# expansion-original-.net
KiCad netlist of a schematic drawn in EAGLE
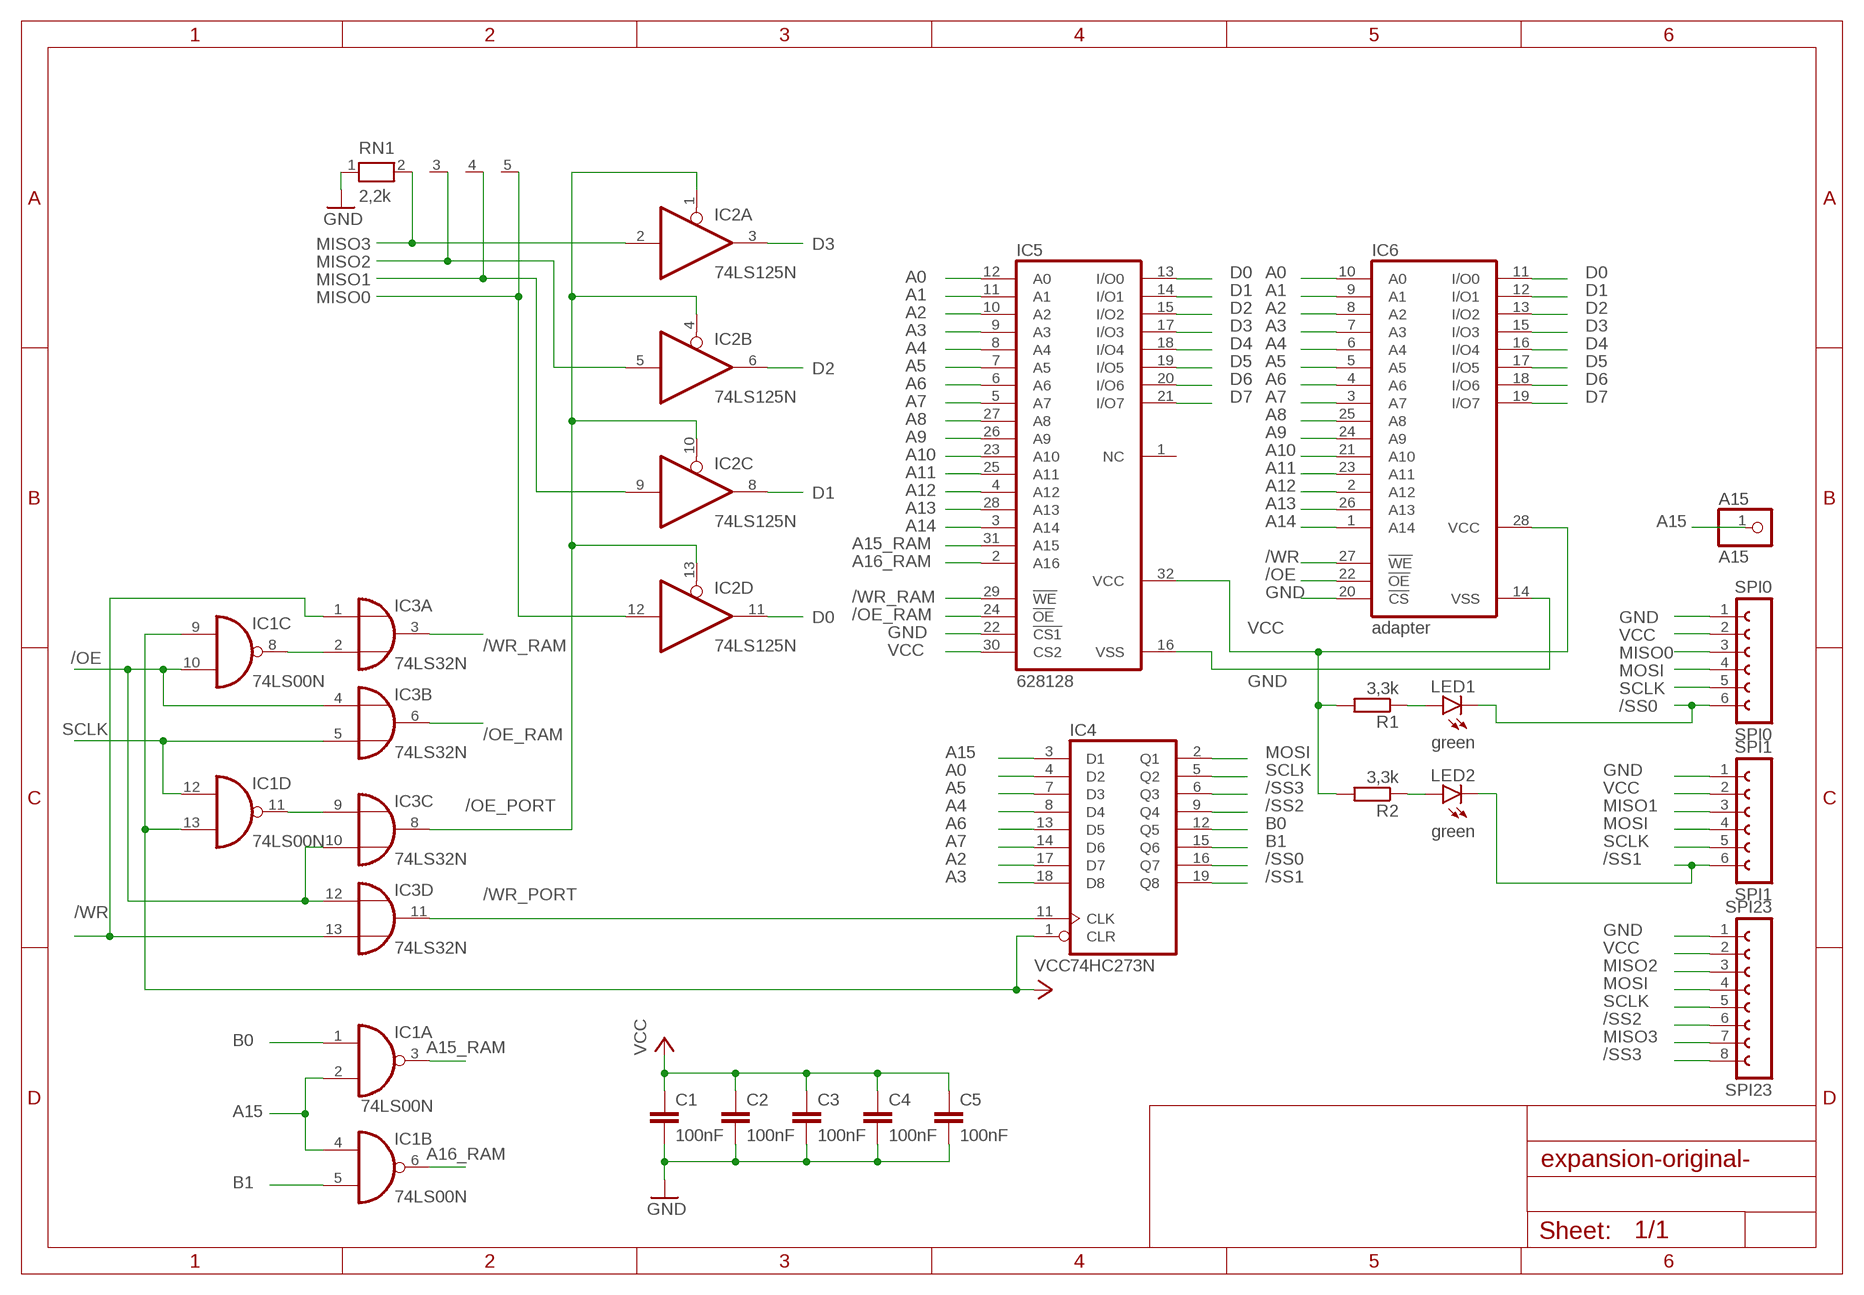
[diagram p0: schematic, sheet 1]

(export (version "E")
  (design (tool "Eeschema 10.0.6"))
  (components
    (comp (ref "A15")
      (value "A15")
      (footprint "eagle-import:1X01")
      (libsource (lib "eagle-import") (part "PINHD-1X1"))
    )
    (comp (ref "C1")
      (value "100nF")
      (footprint "eagle-import:C050-024X044")
      (libsource (lib "eagle-import") (part "C-EU050-024X044"))
    )
    (comp (ref "C2")
      (value "100nF")
      (footprint "eagle-import:C050-024X044")
      (libsource (lib "eagle-import") (part "C-EU050-024X044"))
    )
    (comp (ref "C3")
      (value "100nF")
      (footprint "eagle-import:C050-024X044")
      (libsource (lib "eagle-import") (part "C-EU050-024X044"))
    )
    (comp (ref "C4")
      (value "100nF")
      (footprint "eagle-import:C050-024X044")
      (libsource (lib "eagle-import") (part "C-EU050-024X044"))
    )
    (comp (ref "C5")
      (value "100nF")
      (footprint "eagle-import:C050-024X044")
      (libsource (lib "eagle-import") (part "C-EU050-024X044"))
    )
    (comp (ref "IC1")
      (value "74LS00N")
      (footprint "eagle-import:DIL14")
      (libsource (lib "eagle-import") (part "7400NLS"))
    )
    (comp (ref "IC2")
      (value "74LS125N")
      (footprint "eagle-import:DIL14")
      (libsource (lib "eagle-import") (part "74125NLS"))
    )
    (comp (ref "IC3")
      (value "74LS32N")
      (footprint "eagle-import:DIL14")
      (libsource (lib "eagle-import") (part "7432NLS"))
    )
    (comp (ref "IC4")
      (value "74HC273N")
      (footprint "eagle-import:DIL20")
      (libsource (lib "eagle-import") (part "74273NHC"))
    )
    (comp (ref "IC5")
      (value "628128")
      (footprint "eagle-import:DIL32")
      (libsource (lib "eagle-import") (part "628128P"))
    )
    (comp (ref "IC6")
      (value "adapter")
      (footprint "eagle-import:DIL28-6")
      (libsource (lib "eagle-import") (part "62256P"))
    )
    (comp (ref "LED1")
      (value "green")
      (footprint "eagle-import:LED3MM")
      (libsource (lib "eagle-import") (part "LED3MM"))
    )
    (comp (ref "LED2")
      (value "green")
      (footprint "eagle-import:LED3MM")
      (libsource (lib "eagle-import") (part "LED3MM"))
    )
    (comp (ref "R1")
      (value "3,3k")
      (footprint "eagle-import:0207_10")
      (libsource (lib "eagle-import") (part "R-EU_0207/10"))
    )
    (comp (ref "R2")
      (value "3,3k")
      (footprint "eagle-import:0207_10")
      (libsource (lib "eagle-import") (part "R-EU_0207/10"))
    )
    (comp (ref "RN1")
      (value "2,2k")
      (footprint "eagle-import:RN-5")
      (libsource (lib "eagle-import") (part "RN04"))
    )
    (comp (ref "SPI0")
      (value "SPI0")
      (footprint "eagle-import:FE06")
      (libsource (lib "eagle-import") (part "FE06-1"))
    )
    (comp (ref "SPI1")
      (value "SPI1")
      (footprint "eagle-import:FE06")
      (libsource (lib "eagle-import") (part "FE06-1"))
    )
    (comp (ref "SPI23")
      (value "SPI23")
      (footprint "eagle-import:FE08")
      (libsource (lib "eagle-import") (part "FE08-1"))
    )
  )
  (nets
    (net (code "1") (name "/A0") (class "Default")
      (node (ref "IC4") (pin "4") (pinfunction "D2_4") (pintype "input"))
      (node (ref "IC5") (pin "12") (pinfunction "A0_12") (pintype "input"))
      (node (ref "IC6") (pin "10") (pinfunction "A0_10") (pintype "input"))
    )
    (net (code "2") (name "/A1") (class "Default")
      (node (ref "IC5") (pin "11") (pinfunction "A1_11") (pintype "input"))
      (node (ref "IC6") (pin "9") (pinfunction "A1_9") (pintype "input"))
    )
    (net (code "3") (name "/A2") (class "Default")
      (node (ref "IC4") (pin "17") (pinfunction "D7_17") (pintype "input"))
      (node (ref "IC5") (pin "10") (pinfunction "A2_10") (pintype "input"))
      (node (ref "IC6") (pin "8") (pinfunction "A2_8") (pintype "input"))
    )
    (net (code "4") (name "/A3") (class "Default")
      (node (ref "IC4") (pin "18") (pinfunction "D8_18") (pintype "input"))
      (node (ref "IC5") (pin "9") (pinfunction "A3_9") (pintype "input"))
      (node (ref "IC6") (pin "7") (pinfunction "A3_7") (pintype "input"))
    )
    (net (code "5") (name "/A4") (class "Default")
      (node (ref "IC4") (pin "8") (pinfunction "D4_8") (pintype "input"))
      (node (ref "IC5") (pin "8") (pinfunction "A4_8") (pintype "input"))
      (node (ref "IC6") (pin "6") (pinfunction "A4_6") (pintype "input"))
    )
    (net (code "6") (name "/A5") (class "Default")
      (node (ref "IC4") (pin "7") (pinfunction "D3_7") (pintype "input"))
      (node (ref "IC5") (pin "7") (pinfunction "A5_7") (pintype "input"))
      (node (ref "IC6") (pin "5") (pinfunction "A5_5") (pintype "input"))
    )
    (net (code "7") (name "/A6") (class "Default")
      (node (ref "IC4") (pin "13") (pinfunction "D5_13") (pintype "input"))
      (node (ref "IC5") (pin "6") (pinfunction "A6_6") (pintype "input"))
      (node (ref "IC6") (pin "4") (pinfunction "A6_4") (pintype "input"))
    )
    (net (code "8") (name "/A7") (class "Default")
      (node (ref "IC4") (pin "14") (pinfunction "D6_14") (pintype "input"))
      (node (ref "IC5") (pin "5") (pinfunction "A7_5") (pintype "input"))
      (node (ref "IC6") (pin "3") (pinfunction "A7_3") (pintype "input"))
    )
    (net (code "9") (name "/A8") (class "Default")
      (node (ref "IC5") (pin "27") (pinfunction "A8_27") (pintype "input"))
      (node (ref "IC6") (pin "25") (pinfunction "A8_25") (pintype "input"))
    )
    (net (code "10") (name "/A9") (class "Default")
      (node (ref "IC5") (pin "26") (pinfunction "A9_26") (pintype "input"))
      (node (ref "IC6") (pin "24") (pinfunction "A9_24") (pintype "input"))
    )
    (net (code "11") (name "/A10") (class "Default")
      (node (ref "IC5") (pin "23") (pinfunction "A10_23") (pintype "input"))
      (node (ref "IC6") (pin "21") (pinfunction "A10_21") (pintype "input"))
    )
    (net (code "12") (name "/A11") (class "Default")
      (node (ref "IC5") (pin "25") (pinfunction "A11_25") (pintype "input"))
      (node (ref "IC6") (pin "23") (pinfunction "A11_23") (pintype "input"))
    )
    (net (code "13") (name "/A12") (class "Default")
      (node (ref "IC5") (pin "4") (pinfunction "A12_4") (pintype "input"))
      (node (ref "IC6") (pin "2") (pinfunction "A12_2") (pintype "input"))
    )
    (net (code "14") (name "/A13") (class "Default")
      (node (ref "IC5") (pin "28") (pinfunction "A13_28") (pintype "input"))
      (node (ref "IC6") (pin "26") (pinfunction "A13_26") (pintype "input"))
    )
    (net (code "15") (name "/A14") (class "Default")
      (node (ref "IC5") (pin "3") (pinfunction "A14_3") (pintype "input"))
      (node (ref "IC6") (pin "1") (pinfunction "A14_1") (pintype "input"))
    )
    (net (code "16") (name "/A15") (class "Default")
      (node (ref "A15") (pin "1") (pinfunction "1_1") (pintype "passive"))
      (node (ref "IC1") (pin "2") (pinfunction "I1_2") (pintype "input"))
      (node (ref "IC1") (pin "4") (pinfunction "I0_4") (pintype "input"))
      (node (ref "IC4") (pin "3") (pinfunction "D1_3") (pintype "input"))
    )
    (net (code "17") (name "/A15_RAM") (class "Default")
      (node (ref "IC1") (pin "3") (pinfunction "O_3") (pintype "output"))
      (node (ref "IC5") (pin "31") (pinfunction "A15_31") (pintype "input"))
    )
    (net (code "18") (name "/A16_RAM") (class "Default")
      (node (ref "IC1") (pin "6") (pinfunction "O_6") (pintype "output"))
      (node (ref "IC5") (pin "2") (pinfunction "A16_2") (pintype "input"))
    )
    (net (code "19") (name "/B0") (class "Default")
      (node (ref "IC1") (pin "1") (pinfunction "I0_1") (pintype "input"))
      (node (ref "IC4") (pin "12") (pinfunction "Q5_12") (pintype "output"))
    )
    (net (code "20") (name "/B1") (class "Default")
      (node (ref "IC1") (pin "5") (pinfunction "I1_5") (pintype "input"))
      (node (ref "IC4") (pin "15") (pinfunction "Q6_15") (pintype "output"))
    )
    (net (code "21") (name "/D0") (class "Default")
      (node (ref "IC2") (pin "11") (pinfunction "O_11") (pintype "tri_state"))
      (node (ref "IC5") (pin "13") (pinfunction "I/O0_13") (pintype "bidirectional"))
      (node (ref "IC6") (pin "11") (pinfunction "I/O0_11") (pintype "bidirectional"))
    )
    (net (code "22") (name "/D1") (class "Default")
      (node (ref "IC2") (pin "8") (pinfunction "O_8") (pintype "tri_state"))
      (node (ref "IC5") (pin "14") (pinfunction "I/O1_14") (pintype "bidirectional"))
      (node (ref "IC6") (pin "12") (pinfunction "I/O1_12") (pintype "bidirectional"))
    )
    (net (code "23") (name "/D2") (class "Default")
      (node (ref "IC2") (pin "6") (pinfunction "O_6") (pintype "tri_state"))
      (node (ref "IC5") (pin "15") (pinfunction "I/O2_15") (pintype "bidirectional"))
      (node (ref "IC6") (pin "13") (pinfunction "I/O2_13") (pintype "bidirectional"))
    )
    (net (code "24") (name "/D3") (class "Default")
      (node (ref "IC2") (pin "3") (pinfunction "O_3") (pintype "tri_state"))
      (node (ref "IC5") (pin "17") (pinfunction "I/O3_17") (pintype "bidirectional"))
      (node (ref "IC6") (pin "15") (pinfunction "I/O3_15") (pintype "bidirectional"))
    )
    (net (code "25") (name "/D4") (class "Default")
      (node (ref "IC5") (pin "18") (pinfunction "I/O4_18") (pintype "bidirectional"))
      (node (ref "IC6") (pin "16") (pinfunction "I/O4_16") (pintype "bidirectional"))
    )
    (net (code "26") (name "/D5") (class "Default")
      (node (ref "IC5") (pin "19") (pinfunction "I/O5_19") (pintype "bidirectional"))
      (node (ref "IC6") (pin "17") (pinfunction "I/O5_17") (pintype "bidirectional"))
    )
    (net (code "27") (name "/D6") (class "Default")
      (node (ref "IC5") (pin "20") (pinfunction "I/O6_20") (pintype "bidirectional"))
      (node (ref "IC6") (pin "18") (pinfunction "I/O6_18") (pintype "bidirectional"))
    )
    (net (code "28") (name "/D7") (class "Default")
      (node (ref "IC5") (pin "21") (pinfunction "I/O7_21") (pintype "bidirectional"))
      (node (ref "IC6") (pin "19") (pinfunction "I/O7_19") (pintype "bidirectional"))
    )
    (net (code "29") (name "/MISO0") (class "Default")
      (node (ref "IC2") (pin "12") (pinfunction "I_12") (pintype "input"))
      (node (ref "RN1") (pin "5") (pinfunction "5_5") (pintype "passive"))
      (node (ref "SPI0") (pin "3") (pinfunction "3_3") (pintype "passive"))
    )
    (net (code "30") (name "/MISO1") (class "Default")
      (node (ref "IC2") (pin "9") (pinfunction "I_9") (pintype "input"))
      (node (ref "RN1") (pin "4") (pinfunction "4_4") (pintype "passive"))
      (node (ref "SPI1") (pin "3") (pinfunction "3_3") (pintype "passive"))
    )
    (net (code "31") (name "/MISO2") (class "Default")
      (node (ref "IC2") (pin "5") (pinfunction "I_5") (pintype "input"))
      (node (ref "RN1") (pin "3") (pinfunction "3_3") (pintype "passive"))
      (node (ref "SPI23") (pin "3") (pinfunction "3_3") (pintype "passive"))
    )
    (net (code "32") (name "/MISO3") (class "Default")
      (node (ref "IC2") (pin "2") (pinfunction "I_2") (pintype "input"))
      (node (ref "RN1") (pin "2") (pinfunction "2_2") (pintype "passive"))
      (node (ref "SPI23") (pin "7") (pinfunction "7_7") (pintype "passive"))
    )
    (net (code "33") (name "/MOSI") (class "Default")
      (node (ref "IC4") (pin "2") (pinfunction "Q1_2") (pintype "output"))
      (node (ref "SPI0") (pin "4") (pinfunction "4_4") (pintype "passive"))
      (node (ref "SPI1") (pin "4") (pinfunction "4_4") (pintype "passive"))
      (node (ref "SPI23") (pin "4") (pinfunction "4_4") (pintype "passive"))
    )
    (net (code "34") (name "/SCLK") (class "Default")
      (node (ref "IC1") (pin "12") (pinfunction "I0_12") (pintype "input"))
      (node (ref "IC3") (pin "5") (pinfunction "I1_5") (pintype "input"))
      (node (ref "IC4") (pin "5") (pinfunction "Q2_5") (pintype "output"))
      (node (ref "SPI0") (pin "5") (pinfunction "5_5") (pintype "passive"))
      (node (ref "SPI1") (pin "5") (pinfunction "5_5") (pintype "passive"))
      (node (ref "SPI23") (pin "5") (pinfunction "5_5") (pintype "passive"))
    )
    (net (code "35") (name "/{slash}OE") (class "Default")
      (node (ref "IC1") (pin "10") (pinfunction "I1_10") (pintype "input"))
      (node (ref "IC3") (pin "10") (pinfunction "I1_10") (pintype "input"))
      (node (ref "IC3") (pin "12") (pinfunction "I0_12") (pintype "input"))
      (node (ref "IC3") (pin "4") (pinfunction "I0_4") (pintype "input"))
      (node (ref "IC6") (pin "22") (pinfunction "~{OE}_22") (pintype "input"))
    )
    (net (code "36") (name "/{slash}OE_PORT") (class "Default")
      (node (ref "IC2") (pin "1") (pinfunction "OE_1") (pintype "input"))
      (node (ref "IC2") (pin "10") (pinfunction "OE_10") (pintype "input"))
      (node (ref "IC2") (pin "13") (pinfunction "OE_13") (pintype "input"))
      (node (ref "IC2") (pin "4") (pinfunction "OE_4") (pintype "input"))
      (node (ref "IC3") (pin "8") (pinfunction "O_8") (pintype "output"))
    )
    (net (code "37") (name "/{slash}OE_RAM") (class "Default")
      (node (ref "IC3") (pin "6") (pinfunction "O_6") (pintype "output"))
      (node (ref "IC5") (pin "24") (pinfunction "~{OE}_24") (pintype "input"))
    )
    (net (code "38") (name "/{slash}SS0") (class "Default")
      (node (ref "IC4") (pin "16") (pinfunction "Q7_16") (pintype "output"))
      (node (ref "LED1") (pin "K") (pinfunction "C_K") (pintype "passive"))
      (node (ref "SPI0") (pin "6") (pinfunction "6_6") (pintype "passive"))
    )
    (net (code "39") (name "/{slash}SS1") (class "Default")
      (node (ref "IC4") (pin "19") (pinfunction "Q8_19") (pintype "output"))
      (node (ref "LED2") (pin "K") (pinfunction "C_K") (pintype "passive"))
      (node (ref "SPI1") (pin "6") (pinfunction "6_6") (pintype "passive"))
    )
    (net (code "40") (name "/{slash}SS2") (class "Default")
      (node (ref "IC4") (pin "9") (pinfunction "Q4_9") (pintype "output"))
      (node (ref "SPI23") (pin "6") (pinfunction "6_6") (pintype "passive"))
    )
    (net (code "41") (name "/{slash}SS3") (class "Default")
      (node (ref "IC4") (pin "6") (pinfunction "Q3_6") (pintype "output"))
      (node (ref "SPI23") (pin "8") (pinfunction "8_8") (pintype "passive"))
    )
    (net (code "42") (name "/{slash}WR") (class "Default")
      (node (ref "IC3") (pin "1") (pinfunction "I0_1") (pintype "input"))
      (node (ref "IC3") (pin "13") (pinfunction "I1_13") (pintype "input"))
      (node (ref "IC6") (pin "27") (pinfunction "~{WE}_27") (pintype "input"))
    )
    (net (code "43") (name "/{slash}WR_PORT") (class "Default")
      (node (ref "IC3") (pin "11") (pinfunction "O_11") (pintype "output"))
      (node (ref "IC4") (pin "11") (pinfunction "CLK_11") (pintype "input"))
    )
    (net (code "44") (name "/{slash}WR_RAM") (class "Default")
      (node (ref "IC3") (pin "3") (pinfunction "O_3") (pintype "output"))
      (node (ref "IC5") (pin "29") (pinfunction "~{WE}_29") (pintype "input"))
    )
    (net (code "45") (name "GND") (class "Default")
      (node (ref "C1") (pin "2") (pinfunction "2_2") (pintype "passive"))
      (node (ref "C2") (pin "2") (pinfunction "2_2") (pintype "passive"))
      (node (ref "C3") (pin "2") (pinfunction "2_2") (pintype "passive"))
      (node (ref "C4") (pin "2") (pinfunction "2_2") (pintype "passive"))
      (node (ref "C5") (pin "2") (pinfunction "2_2") (pintype "passive"))
      (node (ref "IC5") (pin "16") (pinfunction "VSS_16") (pintype "power_in"))
      (node (ref "IC5") (pin "22") (pinfunction "~{CS1}_22") (pintype "input"))
      (node (ref "IC6") (pin "14") (pinfunction "VSS_14") (pintype "power_in"))
      (node (ref "IC6") (pin "20") (pinfunction "~{CS}_20") (pintype "input"))
      (node (ref "RN1") (pin "1") (pinfunction "1_1") (pintype "passive"))
      (node (ref "SPI0") (pin "1") (pinfunction "1_1") (pintype "passive"))
      (node (ref "SPI1") (pin "1") (pinfunction "1_1") (pintype "passive"))
      (node (ref "SPI23") (pin "1") (pinfunction "1_1") (pintype "passive"))
    )
    (net (code "46") (name "Net-(IC1C-O)") (class "Default")
      (node (ref "IC1") (pin "8") (pinfunction "O_8") (pintype "output"))
      (node (ref "IC3") (pin "2") (pinfunction "I1_2") (pintype "input"))
    )
    (net (code "47") (name "Net-(IC1D-O)") (class "Default")
      (node (ref "IC1") (pin "11") (pinfunction "O_11") (pintype "output"))
      (node (ref "IC3") (pin "9") (pinfunction "I0_9") (pintype "input"))
    )
    (net (code "48") (name "Net-(LED1-PadA)") (class "Default")
      (node (ref "LED1") (pin "A") (pinfunction "A_A") (pintype "passive"))
      (node (ref "R1") (pin "1") (pinfunction "1_1") (pintype "passive"))
    )
    (net (code "49") (name "Net-(LED2-PadA)") (class "Default")
      (node (ref "LED2") (pin "A") (pinfunction "A_A") (pintype "passive"))
      (node (ref "R2") (pin "1") (pinfunction "1_1") (pintype "passive"))
    )
    (net (code "50") (name "VCC") (class "Default")
      (node (ref "C1") (pin "1") (pinfunction "1_1") (pintype "passive"))
      (node (ref "C2") (pin "1") (pinfunction "1_1") (pintype "passive"))
      (node (ref "C3") (pin "1") (pinfunction "1_1") (pintype "passive"))
      (node (ref "C4") (pin "1") (pinfunction "1_1") (pintype "passive"))
      (node (ref "C5") (pin "1") (pinfunction "1_1") (pintype "passive"))
      (node (ref "IC1") (pin "13") (pinfunction "I1_13") (pintype "input"))
      (node (ref "IC1") (pin "9") (pinfunction "I0_9") (pintype "input"))
      (node (ref "IC4") (pin "1") (pinfunction "CLR_1") (pintype "input"))
      (node (ref "IC5") (pin "30") (pinfunction "CS2_30") (pintype "input"))
      (node (ref "IC5") (pin "32") (pinfunction "VCC_32") (pintype "power_in"))
      (node (ref "IC6") (pin "28") (pinfunction "VCC_28") (pintype "power_in"))
      (node (ref "R1") (pin "2") (pinfunction "2_2") (pintype "passive"))
      (node (ref "R2") (pin "2") (pinfunction "2_2") (pintype "passive"))
      (node (ref "SPI0") (pin "2") (pinfunction "2_2") (pintype "passive"))
      (node (ref "SPI1") (pin "2") (pinfunction "2_2") (pintype "passive"))
      (node (ref "SPI23") (pin "2") (pinfunction "2_2") (pintype "passive"))
    )
    (net (code "51") (name "unconnected-(IC5-NC-Pad1)") (class "Default")
      (node (ref "IC5") (pin "1") (pinfunction "NC_1") (pintype "no_connect"))
    )
  )
)
